# 1_Comb_Generator_Sch.net
KiCad netlist of a schematic drawn in Altium Designer
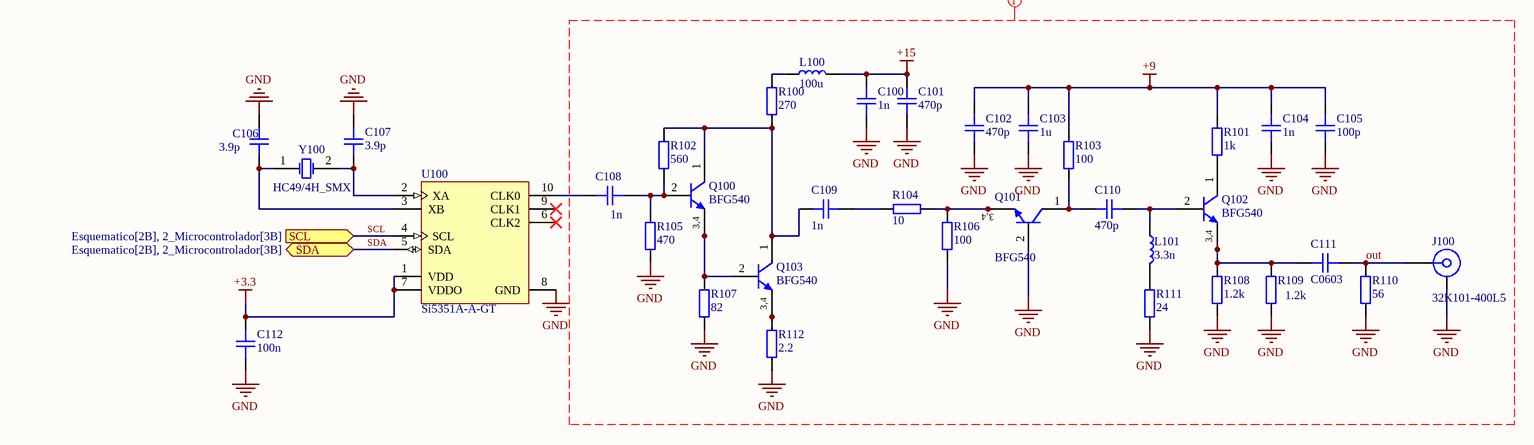
[diagram p0: 1_Comb_Generator_Sch.SchDoc]

(export (version "E")
  (design (tool "Eeschema 10.0.6"))
  (components
    (comp (ref "C100")
      (value "1n")
      (footprint "CAP_0603")
      (description "Capacitor SMD 0603")
      (libsource (lib "Schematic-Lib-PhilsLab") (part "CAP_0603"))
    )
    (comp (ref "C101")
      (value "470p")
      (footprint "CAP_0603")
      (description "Capacitor SMD 0603")
      (libsource (lib "Schematic-Lib-PhilsLab") (part "CAP_0603"))
    )
    (comp (ref "C102")
      (value "470p")
      (footprint "CAP_0603")
      (description "Capacitor SMD 0603")
      (libsource (lib "Schematic-Lib-PhilsLab") (part "CAP_0603"))
    )
    (comp (ref "C103")
      (value "1u")
      (footprint "CAP_0603")
      (description "Capacitor SMD 0603")
      (libsource (lib "Schematic-Lib-PhilsLab") (part "CAP_0603"))
    )
    (comp (ref "C104")
      (value "1n")
      (footprint "CAP_0603")
      (description "Capacitor SMD 0603")
      (libsource (lib "Schematic-Lib-PhilsLab") (part "CAP_0603"))
    )
    (comp (ref "C105")
      (value "100p")
      (footprint "CAP_0603")
      (description "Capacitor SMD 0603")
      (libsource (lib "Schematic-Lib-PhilsLab") (part "CAP_0603"))
    )
    (comp (ref "C106")
      (value "3.9p")
      (footprint "CAP_0603")
      (description "Capacitor SMD 0603")
      (libsource (lib "Schematic-Lib-PhilsLab") (part "CAP_0603"))
    )
    (comp (ref "C107")
      (value "3.9p")
      (footprint "CAP_0603")
      (description "Capacitor SMD 0603")
      (libsource (lib "Schematic-Lib-PhilsLab") (part "CAP_0603"))
    )
    (comp (ref "C108")
      (value "1n")
      (footprint "CAP_0603")
      (description "Capacitor SMD 0603")
      (libsource (lib "Schematic-Lib-PhilsLab") (part "CAP_0603"))
    )
    (comp (ref "C109")
      (value "1n")
      (footprint "CAP_0603")
      (description "Capacitor SMD 0603")
      (libsource (lib "Schematic-Lib-PhilsLab") (part "CAP_0603"))
    )
    (comp (ref "C110")
      (value "470p")
      (footprint "CAP_0603")
      (description "Capacitor SMD 0603")
      (libsource (lib "Schematic-Lib-PhilsLab") (part "CAP_0603"))
    )
    (comp (ref "C111")
      (value "C0603")
      (footprint "CAP_0603")
      (description "Capacitor SMD 0603")
      (libsource (lib "Schematic-Lib-PhilsLab") (part "CAP_0603"))
    )
    (comp (ref "C112")
      (value "100n")
      (footprint "CAP_0603")
      (description "Capacitor SMD 0603")
      (libsource (lib "Schematic-Lib-PhilsLab") (part "CAP_0603"))
    )
    (comp (ref "J100")
      (value "32K101-400L5")
      (footprint "ROS-32K101-400L5_V")
      (description "SMA Straight Jack, Up to 18 GHz, -55 to 155 degC")
      (fields (field (name "MANUFACTURER") "Rosenberger"))
      (libsource (lib "Altium Content Vault") (part "ROS-CN-1F-RF1"))
    )
    (comp (ref "L100")
      (value "100u")
      (footprint "IND_0603")
      (description "Inductor SMD 0603")
      (libsource (lib "Schematic-Lib-PhilsLab") (part "IND_0603"))
    )
    (comp (ref "L101")
      (value "3.3n")
      (footprint "IND_0603")
      (description "Inductor SMD 0603")
      (libsource (lib "") (part "IND_0603_1"))
    )
    (comp (ref "Q100")
      (value "BFG540")
      (footprint "SOT143B_N")
      (description "NPN 9 GHz Wideband Transistor")
      (fields (field (name "PUBLISHER") "Altium Limited"))
      (libsource (lib "Philips Discrete BJT - RF Transistor") (part "BFG540"))
    )
    (comp (ref "Q101")
      (value "BFG540")
      (footprint "SOT143B_N")
      (description "NPN 9 GHz Wideband Transistor")
      (fields (field (name "PUBLISHER") "Altium Limited"))
      (libsource (lib "Philips Discrete BJT - RF Transistor") (part "BFG540"))
    )
    (comp (ref "Q102")
      (value "BFG540")
      (footprint "SOT143B_N")
      (description "NPN 9 GHz Wideband Transistor")
      (fields (field (name "PUBLISHER") "Altium Limited"))
      (libsource (lib "Philips Discrete BJT - RF Transistor") (part "BFG540"))
    )
    (comp (ref "Q103")
      (value "BFG540")
      (footprint "SOT143B_N")
      (description "NPN 9 GHz Wideband Transistor")
      (fields (field (name "PUBLISHER") "Altium Limited"))
      (libsource (lib "Philips Discrete BJT - RF Transistor") (part "BFG540"))
    )
    (comp (ref "R100")
      (value "270")
      (footprint "RES_0603")
      (description "Resistor SMD 0603")
      (libsource (lib "Schematic-Lib-PhilsLab") (part "RES_0603"))
    )
    (comp (ref "R101")
      (value "1k")
      (footprint "RES_0603")
      (description "Resistor SMD 0603")
      (libsource (lib "Schematic-Lib-PhilsLab") (part "RES_0603"))
    )
    (comp (ref "R102")
      (value "560")
      (footprint "RES_0603")
      (description "Resistor SMD 0603")
      (libsource (lib "Schematic-Lib-PhilsLab") (part "RES_0603"))
    )
    (comp (ref "R103")
      (value "100")
      (footprint "RES_0603")
      (description "Resistor SMD 0603")
      (libsource (lib "Schematic-Lib-PhilsLab") (part "RES_0603"))
    )
    (comp (ref "R104")
      (value "10")
      (footprint "RES_0603")
      (description "Resistor SMD 0603")
      (libsource (lib "Schematic-Lib-PhilsLab") (part "RES_0603"))
    )
    (comp (ref "R105")
      (value "470")
      (footprint "RES_0603")
      (description "Resistor SMD 0603")
      (libsource (lib "Schematic-Lib-PhilsLab") (part "RES_0603"))
    )
    (comp (ref "R106")
      (value "100")
      (footprint "RES_0603")
      (description "Resistor SMD 0603")
      (libsource (lib "Schematic-Lib-PhilsLab") (part "RES_0603"))
    )
    (comp (ref "R107")
      (value "82")
      (footprint "RES_0603")
      (description "Resistor SMD 0603")
      (libsource (lib "Schematic-Lib-PhilsLab") (part "RES_0603"))
    )
    (comp (ref "R108")
      (value "1.2k")
      (footprint "RES_0603")
      (description "Resistor SMD 0603")
      (libsource (lib "Schematic-Lib-PhilsLab") (part "RES_0603"))
    )
    (comp (ref "R109")
      (value "1.2k")
      (footprint "RES_0603")
      (description "Resistor SMD 0603")
      (libsource (lib "Schematic-Lib-PhilsLab") (part "RES_0603"))
    )
    (comp (ref "R110")
      (value "56")
      (footprint "RES_0603")
      (description "Resistor SMD 0603")
      (libsource (lib "Schematic-Lib-PhilsLab") (part "RES_0603"))
    )
    (comp (ref "R111")
      (value "24")
      (footprint "RES_0603")
      (description "Resistor SMD 0603")
      (libsource (lib "Schematic-Lib-PhilsLab") (part "RES_0603"))
    )
    (comp (ref "R112")
      (value "2.2")
      (footprint "RES_0603")
      (description "Resistor SMD 0603")
      (libsource (lib "Schematic-Lib-PhilsLab") (part "RES_0603"))
    )
    (comp (ref "U100")
      (value "Si5351A-A-GT")
      (footprint "SLAB-MSOP-10_N")
      (fields (field (name "MANUFACTURER") "Silicon Labs"))
      (libsource (lib "Silicon Labs Clocks and Oscillators") (part "Si5351A-A-GT"))
    )
    (comp (ref "Y100")
      (value "HC49/4H_SMX")
      (footprint "HC49/4H_SMX")
      (description "Surface Mount Quartz Crystal")
      (fields (field (name "PUBLISHER") "Altium Limited"))
      (libsource (lib "C-MAC Crystal Oscillator") (part "HC49/4H_SMX"))
    )
  )
  (nets
    (net (code "1") (name "+3.3") (class "Default")
      (node (ref "C112") (pin "1") (pinfunction "1_1") (pintype "passive"))
      (node (ref "U100") (pin "1") (pinfunction "VDD_1") (pintype "power_in"))
      (node (ref "U100") (pin "7") (pinfunction "VDDO_7") (pintype "power_in"))
    )
    (net (code "2") (name "+9") (class "Default")
      (node (ref "C102") (pin "1") (pinfunction "1_1") (pintype "passive"))
      (node (ref "C103") (pin "1") (pinfunction "1_1") (pintype "passive"))
      (node (ref "C104") (pin "1") (pinfunction "1_1") (pintype "passive"))
      (node (ref "C105") (pin "1") (pinfunction "1_1") (pintype "passive"))
      (node (ref "R101") (pin "2") (pinfunction "2_2") (pintype "passive"))
      (node (ref "R103") (pin "2") (pinfunction "2_2") (pintype "passive"))
    )
    (net (code "3") (name "+15") (class "Default")
      (node (ref "C100") (pin "1") (pinfunction "1_1") (pintype "passive"))
      (node (ref "C101") (pin "1") (pinfunction "1_1") (pintype "passive"))
      (node (ref "L100") (pin "1") (pinfunction "1_1") (pintype "passive"))
    )
    (net (code "4") (name "/SCL") (class "Default")
      (node (ref "U100") (pin "4") (pinfunction "SCL_4") (pintype "input"))
    )
    (net (code "5") (name "/SDA") (class "Default")
      (node (ref "U100") (pin "5") (pinfunction "SDA_5") (pintype "bidirectional"))
    )
    (net (code "6") (name "/out") (class "Default")
      (node (ref "C111") (pin "2") (pinfunction "2_2") (pintype "passive"))
      (node (ref "J100") (pin "1") (pinfunction "1_1") (pintype "passive"))
      (node (ref "R110") (pin "2") (pinfunction "2_2") (pintype "passive"))
    )
    (net (code "7") (name "GND") (class "Default")
      (node (ref "C100") (pin "2") (pinfunction "2_2") (pintype "passive"))
      (node (ref "C101") (pin "2") (pinfunction "2_2") (pintype "passive"))
      (node (ref "C102") (pin "2") (pinfunction "2_2") (pintype "passive"))
      (node (ref "C103") (pin "2") (pinfunction "2_2") (pintype "passive"))
      (node (ref "C104") (pin "2") (pinfunction "2_2") (pintype "passive"))
      (node (ref "C105") (pin "2") (pinfunction "2_2") (pintype "passive"))
      (node (ref "C106") (pin "2") (pinfunction "2_2") (pintype "passive"))
      (node (ref "C107") (pin "2") (pinfunction "2_2") (pintype "passive"))
      (node (ref "C112") (pin "2") (pinfunction "2_2") (pintype "passive"))
      (node (ref "J100") (pin "MH") (pinfunction "MH_MH") (pintype "passive"))
      (node (ref "Q101") (pin "2") (pinfunction "B_2") (pintype "passive"))
      (node (ref "R105") (pin "1") (pinfunction "1_1") (pintype "passive"))
      (node (ref "R106") (pin "1") (pinfunction "1_1") (pintype "passive"))
      (node (ref "R107") (pin "1") (pinfunction "1_1") (pintype "passive"))
      (node (ref "R108") (pin "1") (pinfunction "1_1") (pintype "passive"))
      (node (ref "R109") (pin "1") (pinfunction "1_1") (pintype "passive"))
      (node (ref "R110") (pin "1") (pinfunction "1_1") (pintype "passive"))
      (node (ref "R111") (pin "1") (pinfunction "1_1") (pintype "passive"))
      (node (ref "R112") (pin "1") (pinfunction "1_1") (pintype "passive"))
      (node (ref "U100") (pin "8") (pinfunction "GND_8") (pintype "power_in"))
    )
    (net (code "8") (name "Net-(C109-Pad2)") (class "Default")
      (node (ref "C109") (pin "2") (pinfunction "2_2") (pintype "passive"))
      (node (ref "R104") (pin "2") (pinfunction "2_2") (pintype "passive"))
    )
    (net (code "9") (name "Net-(C111-Pad1)") (class "Default")
      (node (ref "C111") (pin "1") (pinfunction "1_1") (pintype "passive"))
      (node (ref "Q102") (pin "3") (pinfunction "E_3") (pintype "passive"))
      (node (ref "Q102") (pin "4") (pinfunction "E_4") (pintype "passive"))
      (node (ref "R108") (pin "2") (pinfunction "2_2") (pintype "passive"))
      (node (ref "R109") (pin "2") (pinfunction "2_2") (pintype "passive"))
    )
    (net (code "10") (name "Net-(L100-Pad2)") (class "Default")
      (node (ref "L100") (pin "2") (pinfunction "2_2") (pintype "passive"))
      (node (ref "R100") (pin "2") (pinfunction "2_2") (pintype "passive"))
    )
    (net (code "11") (name "Net-(L101-Pad2)") (class "Default")
      (node (ref "L101") (pin "2") (pinfunction "2_2") (pintype "passive"))
      (node (ref "R111") (pin "2") (pinfunction "2_2") (pintype "passive"))
    )
    (net (code "12") (name "Net-(Q100-B)") (class "Default")
      (node (ref "C108") (pin "1") (pinfunction "1_1") (pintype "passive"))
      (node (ref "Q100") (pin "2") (pinfunction "B_2") (pintype "passive"))
      (node (ref "R102") (pin "1") (pinfunction "1_1") (pintype "passive"))
      (node (ref "R105") (pin "2") (pinfunction "2_2") (pintype "passive"))
    )
    (net (code "13") (name "Net-(Q100-C)") (class "Default")
      (node (ref "C109") (pin "1") (pinfunction "1_1") (pintype "passive"))
      (node (ref "Q100") (pin "1") (pinfunction "C_1") (pintype "passive"))
      (node (ref "Q103") (pin "1") (pinfunction "C_1") (pintype "passive"))
      (node (ref "R100") (pin "1") (pinfunction "1_1") (pintype "passive"))
      (node (ref "R102") (pin "2") (pinfunction "2_2") (pintype "passive"))
    )
    (net (code "14") (name "Net-(Q101-C)") (class "Default")
      (node (ref "C110") (pin "2") (pinfunction "2_2") (pintype "passive"))
      (node (ref "Q101") (pin "1") (pinfunction "C_1") (pintype "passive"))
      (node (ref "R103") (pin "1") (pinfunction "1_1") (pintype "passive"))
    )
    (net (code "15") (name "Net-(Q101-E-Pad3)") (class "Default")
      (node (ref "Q101") (pin "3") (pinfunction "E_3") (pintype "passive"))
      (node (ref "Q101") (pin "4") (pinfunction "E_4") (pintype "passive"))
      (node (ref "R104") (pin "1") (pinfunction "1_1") (pintype "passive"))
      (node (ref "R106") (pin "2") (pinfunction "2_2") (pintype "passive"))
    )
    (net (code "16") (name "Net-(Q102-B)") (class "Default")
      (node (ref "C110") (pin "1") (pinfunction "1_1") (pintype "passive"))
      (node (ref "L101") (pin "1") (pinfunction "1_1") (pintype "passive"))
      (node (ref "Q102") (pin "2") (pinfunction "B_2") (pintype "passive"))
    )
    (net (code "17") (name "Net-(Q102-C)") (class "Default")
      (node (ref "Q102") (pin "1") (pinfunction "C_1") (pintype "passive"))
      (node (ref "R101") (pin "1") (pinfunction "1_1") (pintype "passive"))
    )
    (net (code "18") (name "Net-(Q103-B)") (class "Default")
      (node (ref "Q100") (pin "3") (pinfunction "E_3") (pintype "passive"))
      (node (ref "Q100") (pin "4") (pinfunction "E_4") (pintype "passive"))
      (node (ref "Q103") (pin "2") (pinfunction "B_2") (pintype "passive"))
      (node (ref "R107") (pin "2") (pinfunction "2_2") (pintype "passive"))
    )
    (net (code "19") (name "Net-(Q103-E-Pad3)") (class "Default")
      (node (ref "Q103") (pin "3") (pinfunction "E_3") (pintype "passive"))
      (node (ref "Q103") (pin "4") (pinfunction "E_4") (pintype "passive"))
      (node (ref "R112") (pin "2") (pinfunction "2_2") (pintype "passive"))
    )
    (net (code "20") (name "Net-(U100-CLK0)") (class "Default")
      (node (ref "C108") (pin "2") (pinfunction "2_2") (pintype "passive"))
      (node (ref "U100") (pin "10") (pinfunction "CLK0_10") (pintype "tri_state"))
    )
    (net (code "21") (name "Net-(U100-XA)") (class "Default")
      (node (ref "C107") (pin "1") (pinfunction "1_1") (pintype "passive"))
      (node (ref "U100") (pin "2") (pinfunction "XA_2") (pintype "input"))
      (node (ref "Y100") (pin "2") (pinfunction "OSC2_2") (pintype "passive"))
    )
    (net (code "22") (name "Net-(U100-XB)") (class "Default")
      (node (ref "C106") (pin "1") (pinfunction "1_1") (pintype "passive"))
      (node (ref "U100") (pin "3") (pinfunction "XB_3") (pintype "passive"))
      (node (ref "Y100") (pin "1") (pinfunction "OSC1_1") (pintype "passive"))
    )
    (net (code "23") (name "unconnected-(U100-CLK1-Pad9)") (class "Default")
      (node (ref "U100") (pin "9") (pinfunction "CLK1_9") (pintype "tri_state+no_connect"))
    )
    (net (code "24") (name "unconnected-(U100-CLK2-Pad6)") (class "Default")
      (node (ref "U100") (pin "6") (pinfunction "CLK2_6") (pintype "tri_state+no_connect"))
    )
  )
)
